# IMU.net
KiCad netlist of a schematic drawn in Altium Designer
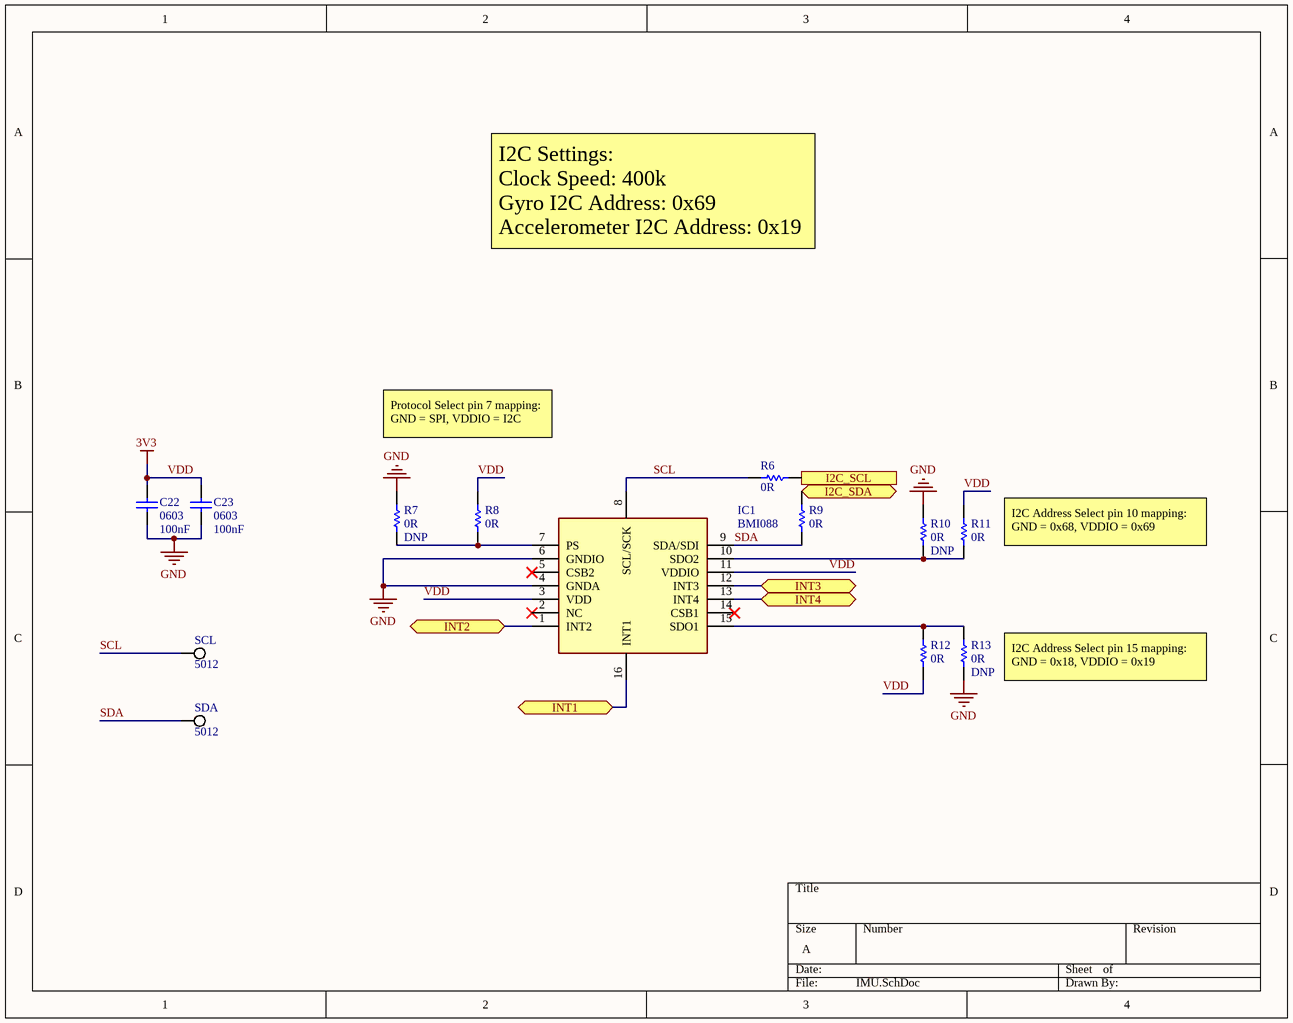
[diagram p0: IMU.SchDoc]

(export (version "E")
  (design (tool "Eeschema 10.0.6"))
  (components
    (comp (ref "C22")
      (value "C0603X104K5RACTU")
      (footprint "CAPC1608X87X35NL15T15")
      (fields
        (field (name "MANUFACTURER") "Kemet")
        (field (name "CASE CODE (IMPERIAL)") "0603")
        (field (name "CAPACITANCE") "100nF")
        (field (name "TOLERANCE") "10%")
        (field (name "VOLTAGE") "50V")
      )
      (libsource (lib "Altium Content Vault") (part "CAP"))
    )
    (comp (ref "C23")
      (value "C0603X104K5RACTU")
      (footprint "CAPC1608X87X35NL15T15")
      (fields
        (field (name "MANUFACTURER") "Kemet")
        (field (name "CASE CODE (IMPERIAL)") "0603")
        (field (name "CAPACITANCE") "100nF")
        (field (name "TOLERANCE") "10%")
        (field (name "VOLTAGE") "50V")
      )
      (libsource (lib "Altium Content Vault") (part "CAP"))
    )
    (comp (ref "IC1")
      (value "BMI088")
      (footprint "SamacSys:BMI088")
      (description "Integrated Circuit")
      (fields (field (name "MOUSER PART NUMBER") "262-BMI088"))
      (libsource (lib "*") (part "BMI088"))
    )
    (comp (ref "R6")
      (value "RC0805JR-100RL")
      (footprint "RESC2013X60X35LL10T20")
      (description "Chip Resistor, 0 Ohm, +/- 5%, 125 mW, -55 to 155 degC, 0805 (2012 Metric), RoHS, Tape and Reel")
      (fields (field (name "MANUFACTURER") "Yageo") (field (name "RESISTANCE") "0R"))
      (libsource (lib "Altium Content Vault") (part "RES-2"))
    )
    (comp (ref "R7")
      (value "RC0805JR-100RL")
      (footprint "RESC2013X60X35LL10T20")
      (description "Chip Resistor, 0 Ohm, +/- 5%, 125 mW, -55 to 155 degC, 0805 (2012 Metric), RoHS, Tape and Reel")
      (fields
        (field (name "MANUFACTURER") "Yageo")
        (field (name "RESISTANCE") "0R")
        (field (name "DNP") "DNP")
      )
      (libsource (lib "Altium Content Vault") (part "RES-2"))
    )
    (comp (ref "R8")
      (value "RC0805JR-100RL")
      (footprint "RESC2013X60X35LL10T20")
      (description "Chip Resistor, 0 Ohm, +/- 5%, 125 mW, -55 to 155 degC, 0805 (2012 Metric), RoHS, Tape and Reel")
      (fields (field (name "MANUFACTURER") "Yageo") (field (name "RESISTANCE") "0R"))
      (libsource (lib "Altium Content Vault") (part "RES-2"))
    )
    (comp (ref "R9")
      (value "RC0805JR-100RL")
      (footprint "RESC2013X60X35LL10T20")
      (description "Chip Resistor, 0 Ohm, +/- 5%, 125 mW, -55 to 155 degC, 0805 (2012 Metric), RoHS, Tape and Reel")
      (fields (field (name "MANUFACTURER") "Yageo") (field (name "RESISTANCE") "0R"))
      (libsource (lib "Altium Content Vault") (part "RES-2"))
    )
    (comp (ref "R10")
      (value "RC0805JR-100RL")
      (footprint "RESC2013X60X35LL10T20")
      (description "Chip Resistor, 0 Ohm, +/- 5%, 125 mW, -55 to 155 degC, 0805 (2012 Metric), RoHS, Tape and Reel")
      (fields
        (field (name "MANUFACTURER") "Yageo")
        (field (name "RESISTANCE") "0R")
        (field (name "DNP") "DNP")
      )
      (libsource (lib "Altium Content Vault") (part "RES-2"))
    )
    (comp (ref "R11")
      (value "RC0805JR-100RL")
      (footprint "RESC2013X60X35LL10T20")
      (description "Chip Resistor, 0 Ohm, +/- 5%, 125 mW, -55 to 155 degC, 0805 (2012 Metric), RoHS, Tape and Reel")
      (fields (field (name "MANUFACTURER") "Yageo") (field (name "RESISTANCE") "0R"))
      (libsource (lib "Altium Content Vault") (part "RES-2"))
    )
    (comp (ref "R12")
      (value "RC0805JR-100RL")
      (footprint "RESC2013X60X35LL10T20")
      (description "Chip Resistor, 0 Ohm, +/- 5%, 125 mW, -55 to 155 degC, 0805 (2012 Metric), RoHS, Tape and Reel")
      (fields (field (name "MANUFACTURER") "Yageo") (field (name "RESISTANCE") "0R"))
      (libsource (lib "Altium Content Vault") (part "RES-2"))
    )
    (comp (ref "R13")
      (value "RC0805JR-100RL")
      (footprint "RESC2013X60X35LL10T20")
      (description "Chip Resistor, 0 Ohm, +/- 5%, 125 mW, -55 to 155 degC, 0805 (2012 Metric), RoHS, Tape and Reel")
      (fields
        (field (name "MANUFACTURER") "Yageo")
        (field (name "RESISTANCE") "0R")
        (field (name "DNP") "DNP")
      )
      (libsource (lib "Altium Content Vault") (part "RES-2"))
    )
    (comp (ref "SCL")
      (value "5012")
      (footprint "KSTN-5012_V")
      (description "Test Point, White, Through Hole, RoHS, Bulk")
      (fields (field (name "MANUFACTURER") "Keystone"))
      (libsource (lib "Altium Content Vault") (part "TESTPOINT_WHITE"))
    )
    (comp (ref "SDA")
      (value "5012")
      (footprint "KSTN-5012_V")
      (description "Test Point, White, Through Hole, RoHS, Bulk")
      (fields (field (name "MANUFACTURER") "Keystone"))
      (libsource (lib "Altium Content Vault") (part "TESTPOINT_WHITE"))
    )
  )
  (nets
    (net (code "1") (name "/I2C_SCL") (class "Default")
      (node (ref "R6") (pin "1") (pinfunction "1_1") (pintype "passive"))
    )
    (net (code "2") (name "/I2C_SDA") (class "Default")
      (node (ref "R9") (pin "2") (pinfunction "2_2") (pintype "passive"))
    )
    (net (code "3") (name "/INT1") (class "Default")
      (node (ref "IC1") (pin "16") (pinfunction "INT1_16") (pintype "passive"))
    )
    (net (code "4") (name "/INT2") (class "Default")
      (node (ref "IC1") (pin "1") (pinfunction "INT2_1") (pintype "passive"))
    )
    (net (code "5") (name "/INT3") (class "Default")
      (node (ref "IC1") (pin "12") (pinfunction "INT3_12") (pintype "passive"))
    )
    (net (code "6") (name "/INT4") (class "Default")
      (node (ref "IC1") (pin "13") (pinfunction "INT4_13") (pintype "passive"))
    )
    (net (code "7") (name "/SCL") (class "Default")
      (node (ref "IC1") (pin "8") (pinfunction "SCL/SCK_8") (pintype "passive"))
      (node (ref "R6") (pin "2") (pinfunction "2_2") (pintype "passive"))
      (node (ref "SCL") (pin "1") (pinfunction "1_1") (pintype "passive"))
    )
    (net (code "8") (name "/SDA") (class "Default")
      (node (ref "IC1") (pin "9") (pinfunction "SDA/SDI_9") (pintype "passive"))
      (node (ref "R9") (pin "1") (pinfunction "1_1") (pintype "passive"))
      (node (ref "SDA") (pin "1") (pinfunction "1_1") (pintype "passive"))
    )
    (net (code "9") (name "3V3") (class "Default")
      (node (ref "C22") (pin "1") (pinfunction "1_1") (pintype "passive"))
      (node (ref "C23") (pin "1") (pinfunction "1_1") (pintype "passive"))
      (node (ref "IC1") (pin "11") (pinfunction "VDDIO_11") (pintype "passive"))
      (node (ref "IC1") (pin "3") (pinfunction "VDD_3") (pintype "passive"))
      (node (ref "R11") (pin "2") (pinfunction "2_2") (pintype "passive"))
      (node (ref "R12") (pin "1") (pinfunction "1_1") (pintype "passive"))
      (node (ref "R8") (pin "2") (pinfunction "2_2") (pintype "passive"))
    )
    (net (code "10") (name "GND") (class "Default")
      (node (ref "C22") (pin "2") (pinfunction "2_2") (pintype "passive"))
      (node (ref "C23") (pin "2") (pinfunction "2_2") (pintype "passive"))
      (node (ref "IC1") (pin "4") (pinfunction "GNDA_4") (pintype "passive"))
      (node (ref "IC1") (pin "6") (pinfunction "GNDIO_6") (pintype "passive"))
      (node (ref "R10") (pin "2") (pinfunction "2_2") (pintype "passive"))
      (node (ref "R13") (pin "1") (pinfunction "1_1") (pintype "passive"))
      (node (ref "R7") (pin "2") (pinfunction "2_2") (pintype "passive"))
    )
    (net (code "11") (name "Net-(IC1-PS)") (class "Default")
      (node (ref "IC1") (pin "7") (pinfunction "PS_7") (pintype "passive"))
      (node (ref "R7") (pin "1") (pinfunction "1_1") (pintype "passive"))
      (node (ref "R8") (pin "1") (pinfunction "1_1") (pintype "passive"))
    )
    (net (code "12") (name "Net-(IC1-SDO1)") (class "Default")
      (node (ref "IC1") (pin "15") (pinfunction "SDO1_15") (pintype "passive"))
      (node (ref "R12") (pin "2") (pinfunction "2_2") (pintype "passive"))
      (node (ref "R13") (pin "2") (pinfunction "2_2") (pintype "passive"))
    )
    (net (code "13") (name "Net-(IC1-SDO2)") (class "Default")
      (node (ref "IC1") (pin "10") (pinfunction "SDO2_10") (pintype "passive"))
      (node (ref "R10") (pin "1") (pinfunction "1_1") (pintype "passive"))
      (node (ref "R11") (pin "1") (pinfunction "1_1") (pintype "passive"))
    )
    (net (code "14") (name "unconnected-(IC1-CSB1-Pad14)") (class "Default")
      (node (ref "IC1") (pin "14") (pinfunction "CSB1_14") (pintype "passive+no_connect"))
    )
    (net (code "15") (name "unconnected-(IC1-CSB2-Pad5)") (class "Default")
      (node (ref "IC1") (pin "5") (pinfunction "CSB2_5") (pintype "passive+no_connect"))
    )
    (net (code "16") (name "unconnected-(IC1-NC-Pad2)") (class "Default")
      (node (ref "IC1") (pin "2") (pinfunction "NC_2") (pintype "passive+no_connect"))
    )
  )
)
